# Tiny_Radio_Reference_Build_V2_RC5_2020-0.net
KiCad netlist of a schematic drawn in EasyEDA
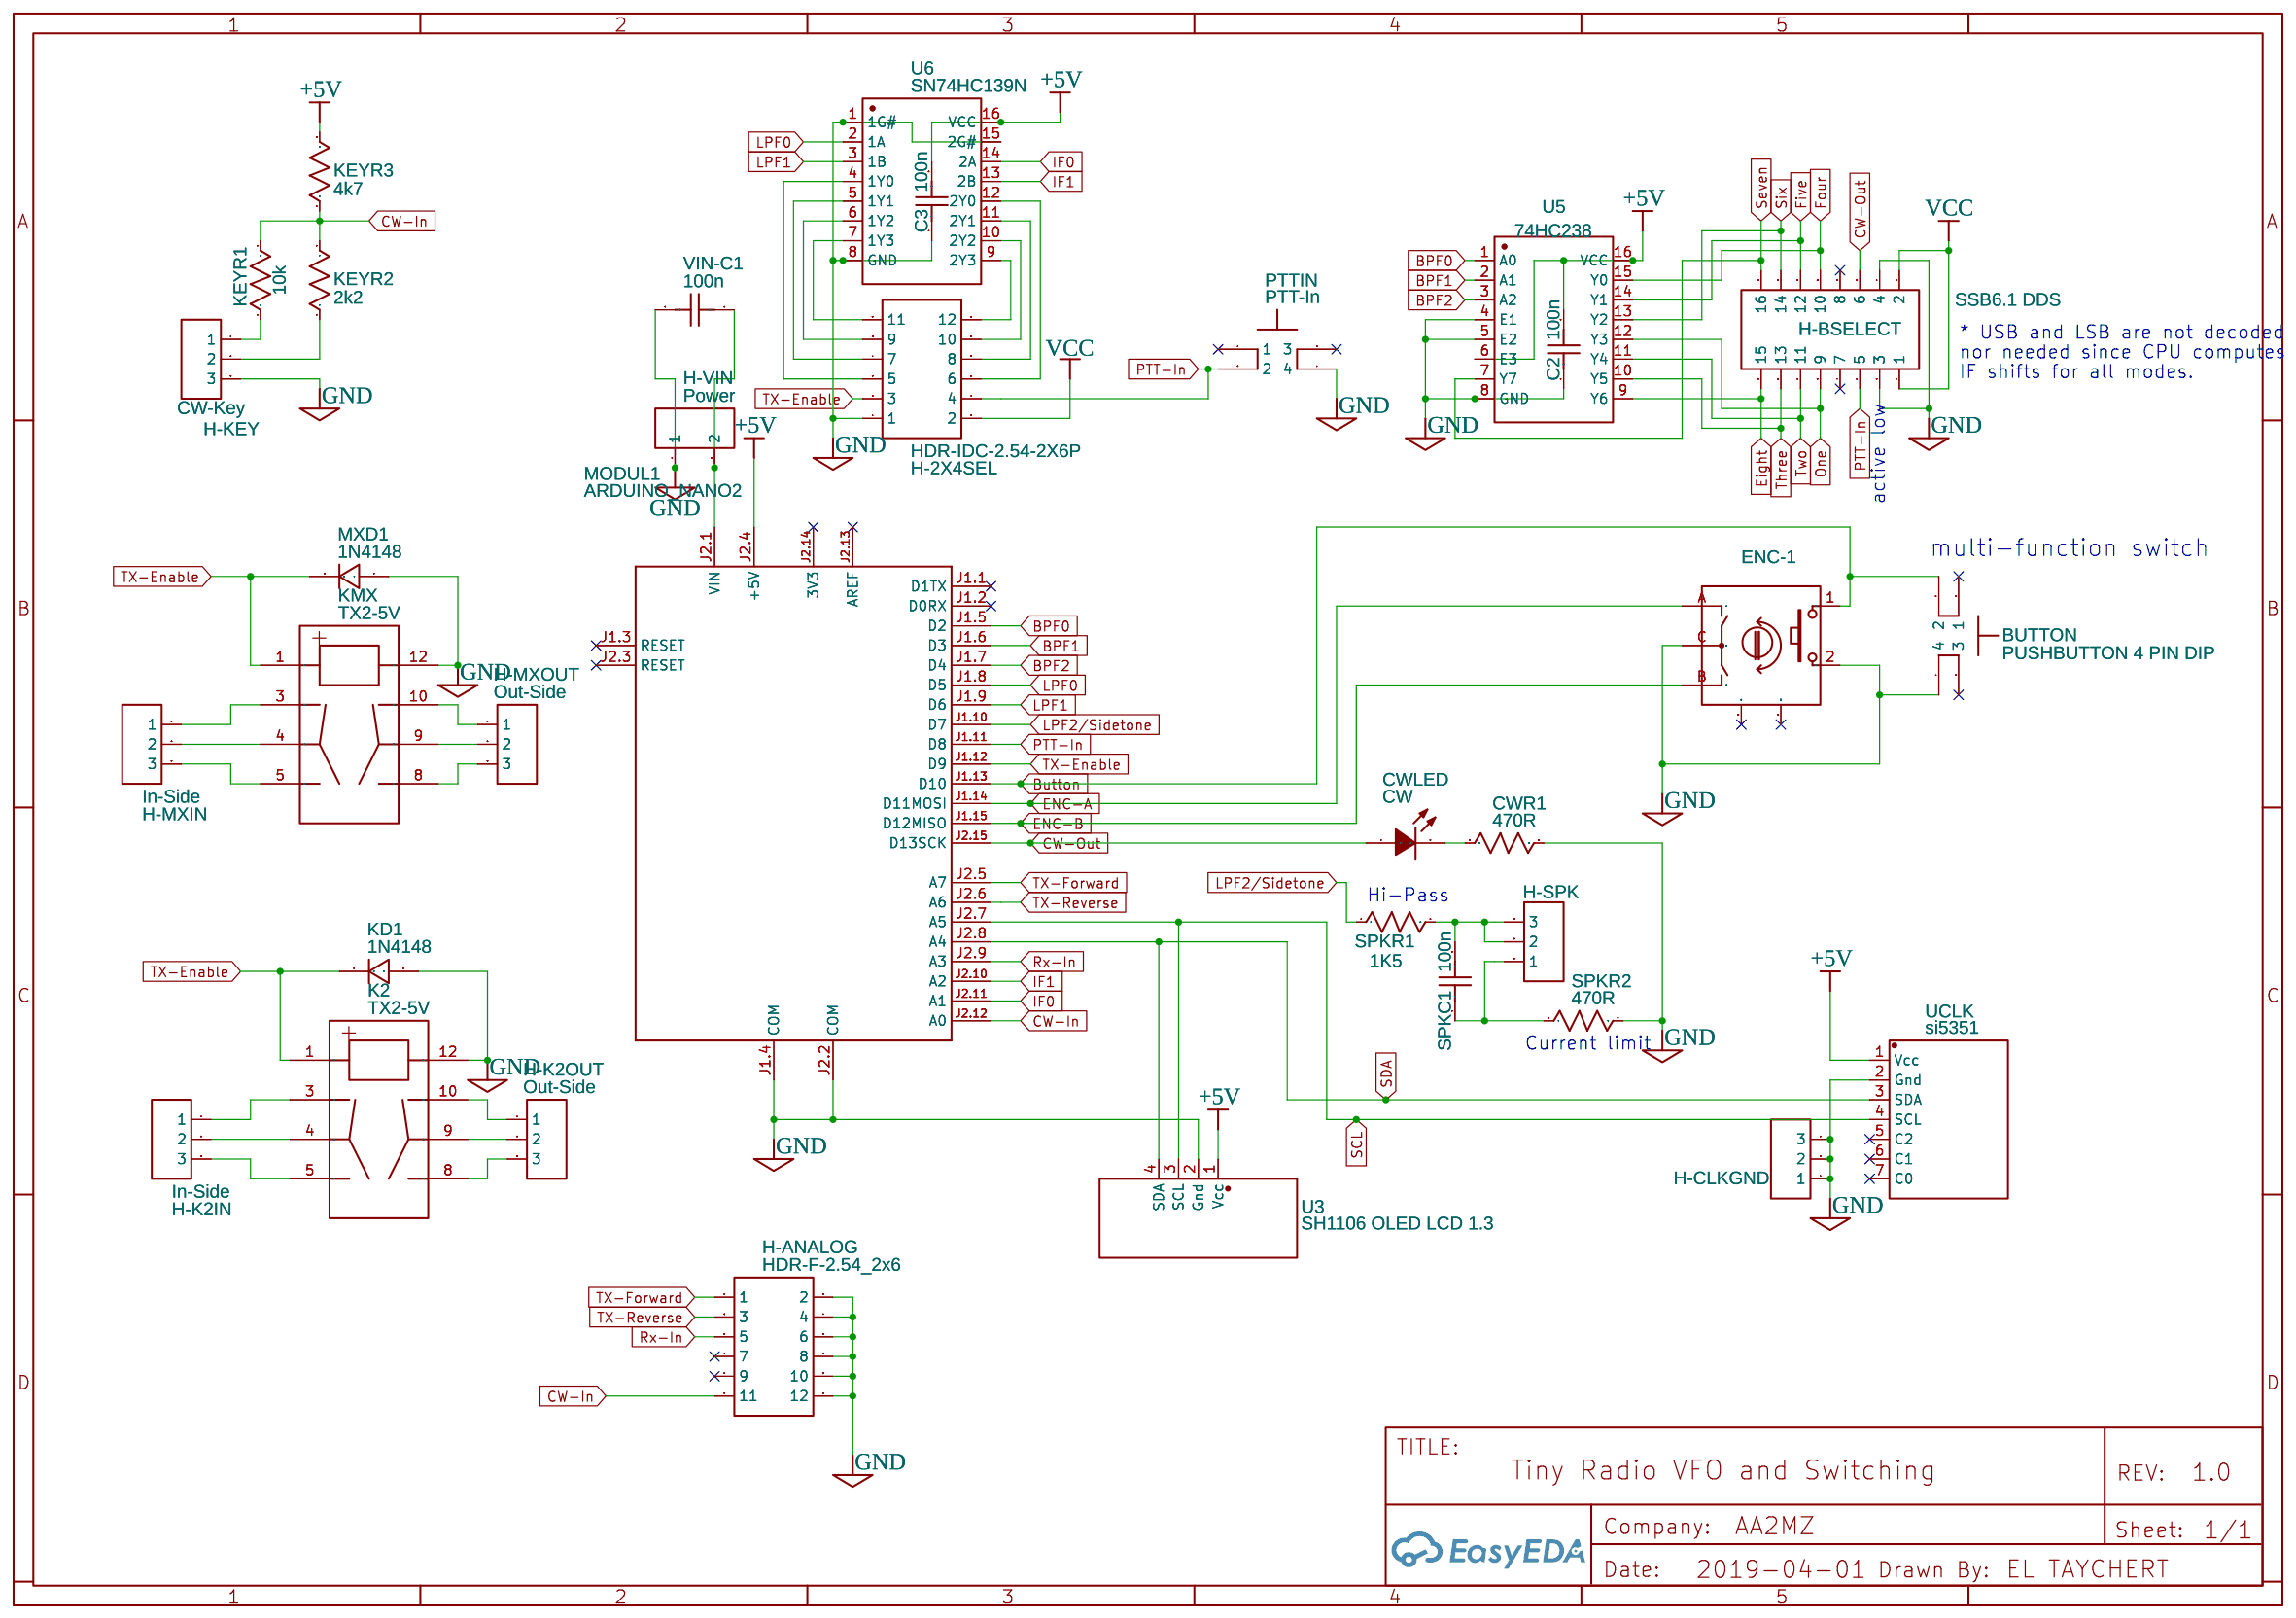
[diagram p0: Sheet_1]
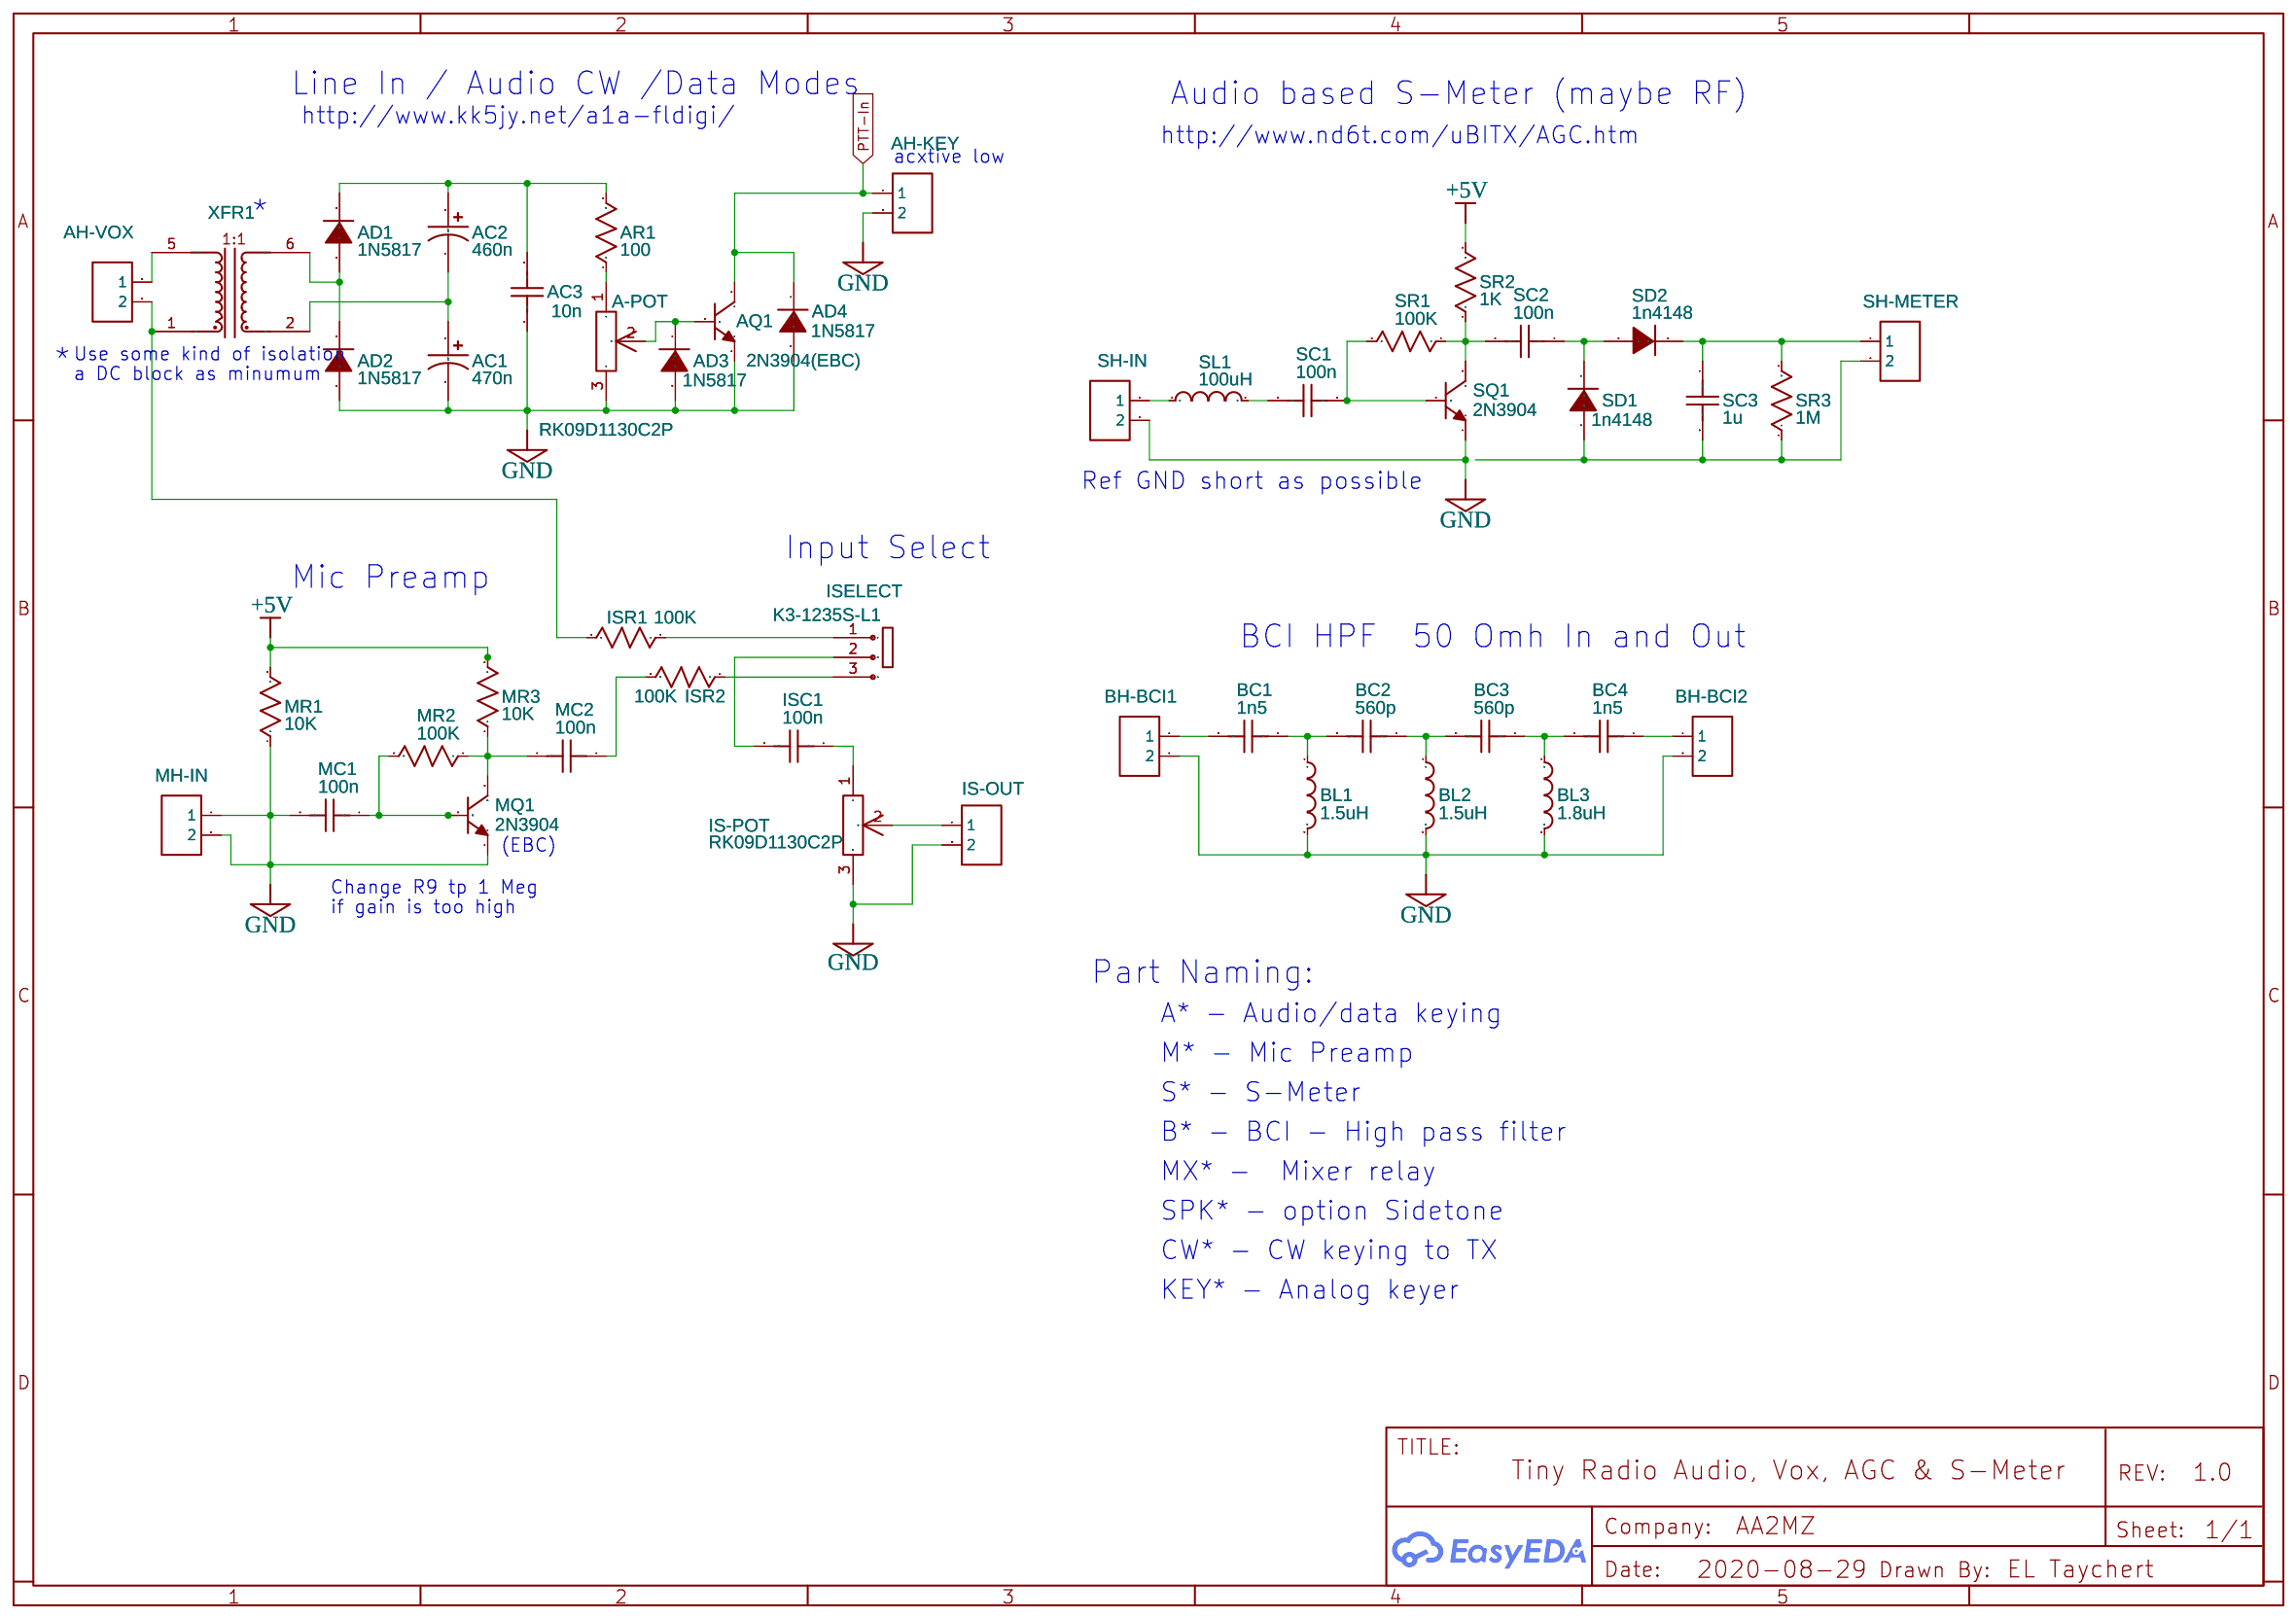
[diagram p1: Sheet_2]

(export (version "E")
  (design (tool "Eeschema 10.0.6"))
  (components
    (comp (ref "BUTTON")
      (value "PUSHBUTTON 4 PIN DIP")
      (fields (field (name "BOM_Manufacturer Part") "Pushbutton"))
      (libsource (lib "") (part "Unknown_985_315"))
    )
    (comp (ref "C2") (value "100n") (libsource (lib "") (part "C_RAD-0.2_US")))
    (comp (ref "C3") (value "100n") (libsource (lib "") (part "C_RAD-0.2_US")))
    (comp (ref "CWLED")
      (value "CW")
      (fields
        (field (name "BOM_Manufacturer Part") "204-10SURD/S530-A3")
        (field (name "BOM_Supplier Part") "C99772")
      )
      (libsource (lib "") (part "Unknown_705_415"))
    )
    (comp (ref "CWR1") (value "470R") (libsource (lib "") (part "Res_AXIAL-0.3(1/8W)_US_2")))
    (comp (ref "ENC-1")
      (value "PEC11R-4015F-S0024")
      (fields (field (name "BOM_Supplier Part") "C143789"))
      (libsource (lib "") (part "Unknown_885_330"))
    )
    (comp (ref "H-2X4SEL")
      (value "HDR-IDC-2.54-2X6P")
      (fields
        (field (name "BOM_Manufacturer Part") "IDC Box 2X6 2.54MM")
        (field (name "BOM_Supplier Part") "C9136")
      )
      (libsource (lib "") (part "HDR-IDC-2.54-2X6P"))
    )
    (comp (ref "H-ANALOG")
      (value "HDR-F-2.54_2x6")
      (fields (field (name "BOM_Supplier Part") "C36191"))
      (libsource (lib "") (part "HDR-F-2.54_2x6"))
    )
    (comp (ref "H-BSELECT")
      (value "SSB6.1 DDS")
      (fields
        (field (name "BOM_Manufacturer Part") "IDC Box 2.54mm 16P　Straight")
        (field (name "BOM_Supplier Part") "C3406")
      )
      (libsource (lib "") (part "HDR-IDC-2.54-2X8P"))
    )
    (comp (ref "H-CLKGND")
      (value "Header-Male-2.54_1x3")
      (fields
        (field (name "BOM_Manufacturer Part") "Header2.54mm 1*3P")
        (field (name "BOM_Supplier Part") "C49257")
      )
      (libsource (lib "") (part "Unknown_905_580"))
    )
    (comp (ref "H-K2IN")
      (value "In-Side")
      (fields
        (field (name "BOM_Manufacturer Part") "Header2.54mm 1*3P")
        (field (name "BOM_Supplier Part") "C49257")
      )
      (libsource (lib "") (part "Unknown_85_570"))
    )
    (comp (ref "H-K2OUT")
      (value "Out-Side")
      (fields
        (field (name "BOM_Manufacturer Part") "Header2.54mm 1*3P")
        (field (name "BOM_Supplier Part") "C49257")
      )
      (libsource (lib "") (part "Unknown_265_570"))
    )
    (comp (ref "H-KEY")
      (value "CW-Key")
      (fields (field (name "BOM_Supplier Part") "C180248"))
      (libsource (lib "") (part "HDR-M-2.54_1x3"))
    )
    (comp (ref "H-MXIN")
      (value "In-Side")
      (fields
        (field (name "BOM_Manufacturer Part") "Header2.54mm 1*3P")
        (field (name "BOM_Supplier Part") "C49257")
      )
      (libsource (lib "") (part "Unknown_70_370"))
    )
    (comp (ref "H-MXOUT")
      (value "Out-Side")
      (fields
        (field (name "BOM_Manufacturer Part") "Header2.54mm 1*3P")
        (field (name "BOM_Supplier Part") "C49257")
      )
      (libsource (lib "") (part "Unknown_250_370"))
    )
    (comp (ref "H-SPK")
      (value "Header-Male-2.54_1x3")
      (fields
        (field (name "BOM_Manufacturer Part") "Header2.54mm 1*3P")
        (field (name "BOM_Supplier Part") "C49257")
      )
      (libsource (lib "") (part "Unknown_770_470"))
    )
    (comp (ref "H-VIN")
      (value "Power")
      (fields (field (name "BOM_Manufacturer Part") "826629-2") (field (name "BOM_Supplier Part") "C86471"))
      (libsource (lib "") (part "Unknown_345_215"))
    )
    (comp (ref "K2")
      (value "TX2-5V")
      (fields (field (name "BOM_Supplier Part") "C192257"))
      (libsource (lib "") (part "TX2-5V_1"))
    )
    (comp (ref "KD1")
      (value "1N4148")
      (fields (field (name "BOM_Supplier Part") "C14516"))
      (libsource (lib "") (part "1N4148"))
    )
    (comp (ref "KEYR1") (value "10k") (libsource (lib "") (part "Res_AXIAL-0.3(1/8W)_US")))
    (comp (ref "KEYR2") (value "2k2") (libsource (lib "") (part "Res_AXIAL-0.3(1/8W)_US")))
    (comp (ref "KEYR3") (value "4k7") (libsource (lib "") (part "Res_AXIAL-0.3(1/8W)_US")))
    (comp (ref "KMX")
      (value "TX2-5V")
      (fields (field (name "BOM_Supplier Part") "C192257"))
      (libsource (lib "") (part "TX2-5V"))
    )
    (comp (ref "MODUL1") (value "ARDUINO_NANO2") (libsource (lib "") (part "ARDUINO_NANO2")))
    (comp (ref "MXD1")
      (value "1N4148")
      (fields (field (name "BOM_Supplier Part") "C14516"))
      (libsource (lib "") (part "1N4148_1"))
    )
    (comp (ref "PTTIN")
      (value "PTT-In")
      (fields (field (name "BOM_Manufacturer Part") "Pushbutton"))
      (libsource (lib "") (part "Unknown_640_170"))
    )
    (comp (ref "SPKC1") (value "100n") (libsource (lib "") (part "C_RAD-0.2_US_1")))
    (comp (ref "SPKR1") (value "1K5") (libsource (lib "") (part "Res_AXIAL-0.3(1/8W)_US_1")))
    (comp (ref "SPKR2") (value "470R") (libsource (lib "") (part "Res_AXIAL-0.3(1/8W)_US_1")))
    (comp (ref "U3")
      (value "SH1106 OLED LCD 1.3")
      (fields (field (name "BOM_Manufacturer Part") "OLED_LCD_SH1106"))
      (libsource (lib "") (part "Unknown_620_590"))
    )
    (comp (ref "U5")
      (value "74HC238")
      (fields
        (field (name "BOM_Manufacturer Part") "CD74HC238E")
        (field (name "BOM_Supplier Part") "820490127")
      )
      (libsource (lib "") (part "Unknown_780_160"))
    )
    (comp (ref "U6")
      (value "SN74HC139N")
      (fields (field (name "BOM_Supplier Part") "C2906"))
      (libsource (lib "") (part "SN74HC139N"))
    )
    (comp (ref "UCLK")
      (value "si5351")
      (fields (field (name "BOM_Manufacturer Part") "?"))
      (libsource (lib "") (part "Unknown_980_560"))
    )
    (comp (ref "VIN-C1") (value "100n") (libsource (lib "") (part "Cap_RAD-0.2_US")))
    (comp (ref "A-POT")
      (value "RK09D1130C2P")
      (fields (field (name "BOM_Supplier Part") "C361173"))
      (libsource (lib "") (part "RK09D1130C2P_1"))
    )
    (comp (ref "AC1") (value "470n") (libsource (lib "") (part "CE_TH_D5.0×F2.0_US")))
    (comp (ref "AC2") (value "460n") (libsource (lib "") (part "CE_TH_D5.0×F2.0_US")))
    (comp (ref "AC3") (value "10n") (libsource (lib "") (part "C_0603_US_4")))
    (comp (ref "AD1")
      (value "1N5817")
      (fields (field (name "BOM_Supplier Part") "C256526"))
      (libsource (lib "") (part "1N5817_C256526"))
    )
    (comp (ref "AD2")
      (value "1N5817")
      (fields (field (name "BOM_Supplier Part") "C256526"))
      (libsource (lib "") (part "1N5817_C256526"))
    )
    (comp (ref "AD3")
      (value "1N5817")
      (fields (field (name "BOM_Supplier Part") "C256526"))
      (libsource (lib "") (part "1N5817_C256526"))
    )
    (comp (ref "AD4")
      (value "1N5817")
      (fields (field (name "BOM_Supplier Part") "C256526"))
      (libsource (lib "") (part "1N5817_C256526"))
    )
    (comp (ref "AH-KEY")
      (value "HDR-M-2.54_1x2")
      (fields (field (name "BOM_Supplier Part") "C124375"))
      (libsource (lib "") (part "HDR-M-2.54_1x2_6"))
    )
    (comp (ref "AH-VOX")
      (value "HDR-M-2.54_1x2")
      (fields (field (name "BOM_Supplier Part") "C124375"))
      (libsource (lib "") (part "HDR-M-2.54_1x2_5"))
    )
    (comp (ref "AQ1")
      (value "2N3904(EBC)")
      (fields (field (name "BOM_Manufacturer Part") "2N3904") (field (name "BOM_Supplier Part") "C118538"))
      (libsource (lib "") (part "2N3904(TO-92)_1"))
    )
    (comp (ref "AR1") (value "100") (libsource (lib "") (part "R_0603_US_4")))
    (comp (ref "BC1") (value "1n5") (libsource (lib "") (part "C_0603_US_3")))
    (comp (ref "BC2") (value "560p") (libsource (lib "") (part "C_0603_US_3")))
    (comp (ref "BC3") (value "560p") (libsource (lib "") (part "C_0603_US_3")))
    (comp (ref "BC4") (value "1n5") (libsource (lib "") (part "C_0603_US_3")))
    (comp (ref "BH-BCI1")
      (value "HDR-M-2.54_1x2")
      (fields (field (name "BOM_Supplier Part") "C124375"))
      (libsource (lib "") (part "HDR-M-2.54_1x2_1"))
    )
    (comp (ref "BH-BCI2")
      (value "HDR-M-2.54_1x2")
      (fields (field (name "BOM_Supplier Part") "C124375"))
      (libsource (lib "") (part "HDR-M-2.54_1x2_7"))
    )
    (comp (ref "BL1") (value "1.5uH") (libsource (lib "") (part "L_AXIAL-0.5_US_2")))
    (comp (ref "BL2") (value "1.5uH") (libsource (lib "") (part "L_AXIAL-0.5_US_2")))
    (comp (ref "BL3") (value "1.8uH") (libsource (lib "") (part "L_AXIAL-0.5_US_1")))
    (comp (ref "IS-OUT")
      (value "HDR-M-2.54_1x2")
      (fields (field (name "BOM_Supplier Part") "C124375"))
      (libsource (lib "") (part "HDR-M-2.54_1x2_2"))
    )
    (comp (ref "IS-POT")
      (value "RK09D1130C2P")
      (fields (field (name "BOM_Supplier Part") "C361173"))
      (libsource (lib "") (part "RK09D1130C2P"))
    )
    (comp (ref "ISC1") (value "100n") (libsource (lib "") (part "C_0603_US")))
    (comp (ref "ISELECT")
      (value "K3-1235S-L1")
      (fields (field (name "BOM_Supplier Part") "C223838"))
      (libsource (lib "") (part "K3-1235S-L1"))
    )
    (comp (ref "ISR1") (value "100K") (libsource (lib "") (part "R_0603_US_2")))
    (comp (ref "ISR2") (value "100K") (libsource (lib "") (part "R_0603_US_2")))
    (comp (ref "MC1") (value "100n") (libsource (lib "") (part "C_0603_US_2")))
    (comp (ref "MC2") (value "100n") (libsource (lib "") (part "C_0603_US_2")))
    (comp (ref "MH-IN")
      (value "HDR-M-2.54_1x2")
      (fields (field (name "BOM_Supplier Part") "C124375"))
      (libsource (lib "") (part "HDR-M-2.54_1x2"))
    )
    (comp (ref "MQ1")
      (value "2N3904")
      (fields (field (name "BOM_Supplier Part") "C118538"))
      (libsource (lib "") (part "2N3904(TO-92)_2"))
    )
    (comp (ref "MR1") (value "10K") (libsource (lib "") (part "R_0603_US_1")))
    (comp (ref "MR2") (value "100K") (libsource (lib "") (part "R_0603_US_3")))
    (comp (ref "MR3") (value "10K") (libsource (lib "") (part "R_0603_US_1")))
    (comp (ref "SC1") (value "100n") (libsource (lib "") (part "C_0603_US_1")))
    (comp (ref "SC2") (value "100n") (libsource (lib "") (part "C_0603_US_1")))
    (comp (ref "SC3") (value "1u") (libsource (lib "") (part "C_0603_US_5")))
    (comp (ref "SD1")
      (value "1n4148")
      (fields (field (name "BOM_Manufacturer Part") "1N5817") (field (name "BOM_Supplier Part") "C256526"))
      (libsource (lib "") (part "1N5817_C256526_1"))
    )
    (comp (ref "SD2")
      (value "1n4148")
      (fields (field (name "BOM_Manufacturer Part") "1N5817") (field (name "BOM_Supplier Part") "C256526"))
      (libsource (lib "") (part "1N5817_C256526_2"))
    )
    (comp (ref "SH-IN")
      (value "HDR-M-2.54_1x2")
      (fields (field (name "BOM_Supplier Part") "C124375"))
      (libsource (lib "") (part "HDR-M-2.54_1x2_3"))
    )
    (comp (ref "SH-METER")
      (value "HDR-M-2.54_1x2")
      (fields (field (name "BOM_Supplier Part") "C124375"))
      (libsource (lib "") (part "HDR-M-2.54_1x2_4"))
    )
    (comp (ref "SL1") (value "100uH") (libsource (lib "") (part "L_AXIAL-0.5_US")))
    (comp (ref "SQ1")
      (value "2N3904")
      (fields (field (name "BOM_Supplier Part") "C118538"))
      (libsource (lib "") (part "2N3904(TO-92)"))
    )
    (comp (ref "SR1") (value "100K") (libsource (lib "") (part "R_0603_US_5")))
    (comp (ref "SR2") (value "1K") (libsource (lib "") (part "R_0603_US")))
    (comp (ref "SR3") (value "1M") (libsource (lib "") (part "R_0603_US")))
    (comp (ref "XFR1")
      (value "HR610660")
      (fields (field (name "BOM_Supplier Part") "C48357"))
      (libsource (lib "") (part "HR610660"))
    )
  )
  (nets
    (net (code "1") (name "+5V") (class "Default")
      (node (ref "C2") (pin "2") (pinfunction "2_2") (pintype "unspecified"))
      (node (ref "C3") (pin "2") (pinfunction "2_2") (pintype "unspecified"))
      (node (ref "KEYR3") (pin "2") (pinfunction "2_2") (pintype "unspecified"))
      (node (ref "MODUL1") (pin "J2.4") (pinfunction "+5V_J2.4") (pintype "passive"))
      (node (ref "MR1") (pin "2") (pinfunction "2_2") (pintype "unspecified"))
      (node (ref "MR3") (pin "2") (pinfunction "2_2") (pintype "unspecified"))
      (node (ref "SR2") (pin "2") (pinfunction "2_2") (pintype "unspecified"))
      (node (ref "U3") (pin "1") (pinfunction "Vcc_1") (pintype "unspecified"))
      (node (ref "U5") (pin "16") (pinfunction "VCC_16") (pintype "unspecified"))
      (node (ref "U5") (pin "6") (pinfunction "E3_6") (pintype "unspecified"))
      (node (ref "U6") (pin "16") (pinfunction "VCC_16") (pintype "unspecified"))
      (node (ref "UCLK") (pin "1") (pinfunction "Vcc_1") (pintype "unspecified"))
    )
    (net (code "2") (name "BPF0") (class "Default")
      (node (ref "MODUL1") (pin "J1.5") (pinfunction "D2_J1.5") (pintype "unspecified"))
      (node (ref "U5") (pin "1") (pinfunction "A0_1") (pintype "unspecified"))
    )
    (net (code "3") (name "BPF1") (class "Default")
      (node (ref "MODUL1") (pin "J1.6") (pinfunction "D3_J1.6") (pintype "unspecified"))
      (node (ref "U5") (pin "2") (pinfunction "A1_2") (pintype "unspecified"))
    )
    (net (code "4") (name "BPF2") (class "Default")
      (node (ref "MODUL1") (pin "J1.7") (pinfunction "D4_J1.7") (pintype "unspecified"))
      (node (ref "U5") (pin "3") (pinfunction "A2_3") (pintype "unspecified"))
    )
    (net (code "5") (name "Button") (class "Default")
      (node (ref "BUTTON") (pin "2") (pinfunction "2_2") (pintype "unspecified"))
      (node (ref "ENC-1") (pin "1") (pinfunction "1_1") (pintype "unspecified"))
      (node (ref "MODUL1") (pin "J1.13") (pinfunction "D10_J1.13") (pintype "unspecified"))
    )
    (net (code "6") (name "CW-In") (class "Default")
      (node (ref "H-ANALOG") (pin "11") (pinfunction "11_11") (pintype "input"))
      (node (ref "KEYR1") (pin "2") (pinfunction "2_2") (pintype "unspecified"))
      (node (ref "KEYR2") (pin "2") (pinfunction "2_2") (pintype "unspecified"))
      (node (ref "KEYR3") (pin "1") (pinfunction "1_1") (pintype "unspecified"))
      (node (ref "MODUL1") (pin "J2.12") (pinfunction "A0_J2.12") (pintype "unspecified"))
    )
    (net (code "7") (name "CW-Out") (class "Default")
      (node (ref "CWLED") (pin "1") (pinfunction "A_1") (pintype "unspecified"))
      (node (ref "H-BSELECT") (pin "6") (pinfunction "6_6") (pintype "unspecified"))
      (node (ref "MODUL1") (pin "J2.15") (pinfunction "D13SCK_J2.15") (pintype "unspecified"))
    )
    (net (code "8") (name "ENC-A") (class "Default")
      (node (ref "ENC-1") (pin "A") (pinfunction "A_A") (pintype "unspecified"))
      (node (ref "MODUL1") (pin "J1.14") (pinfunction "D11MOSI_J1.14") (pintype "unspecified"))
    )
    (net (code "9") (name "ENC-B") (class "Default")
      (node (ref "ENC-1") (pin "B") (pinfunction "B_B") (pintype "unspecified"))
      (node (ref "MODUL1") (pin "J1.15") (pinfunction "D12MISO_J1.15") (pintype "unspecified"))
    )
    (net (code "10") (name "Eight") (class "Default")
      (node (ref "H-BSELECT") (pin "15") (pinfunction "15_15") (pintype "unspecified"))
      (node (ref "U5") (pin "9") (pinfunction "Y6_9") (pintype "unspecified"))
    )
    (net (code "11") (name "Five") (class "Default")
      (node (ref "H-BSELECT") (pin "12") (pinfunction "12_12") (pintype "unspecified"))
      (node (ref "U5") (pin "14") (pinfunction "Y1_14") (pintype "unspecified"))
    )
    (net (code "12") (name "Four") (class "Default")
      (node (ref "H-BSELECT") (pin "10") (pinfunction "10_10") (pintype "unspecified"))
      (node (ref "U5") (pin "15") (pinfunction "Y0_15") (pintype "unspecified"))
    )
    (net (code "13") (name "GND") (class "Default")
      (node (ref "A-POT") (pin "3") (pinfunction "3_3") (pintype "unspecified"))
      (node (ref "AC1") (pin "2") (pinfunction "2_2") (pintype "unspecified"))
      (node (ref "AC3") (pin "1") (pinfunction "1_1") (pintype "unspecified"))
      (node (ref "AD2") (pin "2") (pinfunction "A_2") (pintype "unspecified"))
      (node (ref "AD3") (pin "2") (pinfunction "A_2") (pintype "unspecified"))
      (node (ref "AD4") (pin "2") (pinfunction "A_2") (pintype "unspecified"))
      (node (ref "AH-KEY") (pin "2") (pinfunction "2_2") (pintype "unspecified"))
      (node (ref "AQ1") (pin "1") (pinfunction "E_1") (pintype "unspecified"))
      (node (ref "BH-BCI1") (pin "2") (pinfunction "2_2") (pintype "unspecified"))
      (node (ref "BH-BCI2") (pin "2") (pinfunction "2_2") (pintype "unspecified"))
      (node (ref "BL1") (pin "2") (pinfunction "2_2") (pintype "unspecified"))
      (node (ref "BL2") (pin "2") (pinfunction "2_2") (pintype "unspecified"))
      (node (ref "BL3") (pin "2") (pinfunction "2_2") (pintype "unspecified"))
      (node (ref "BUTTON") (pin "4") (pinfunction "4_4") (pintype "unspecified"))
      (node (ref "C2") (pin "1") (pinfunction "1_1") (pintype "unspecified"))
      (node (ref "C3") (pin "1") (pinfunction "1_1") (pintype "unspecified"))
      (node (ref "CWR1") (pin "2") (pinfunction "2_2") (pintype "unspecified"))
      (node (ref "ENC-1") (pin "2") (pinfunction "2_2") (pintype "unspecified"))
      (node (ref "ENC-1") (pin "C") (pinfunction "C_C") (pintype "unspecified"))
      (node (ref "H-2X4SEL") (pin "1") (pinfunction "1_1") (pintype "unspecified"))
      (node (ref "H-ANALOG") (pin "10") (pinfunction "10_10") (pintype "input"))
      (node (ref "H-ANALOG") (pin "12") (pinfunction "12_12") (pintype "input"))
      (node (ref "H-ANALOG") (pin "2") (pinfunction "2_2") (pintype "input"))
      (node (ref "H-ANALOG") (pin "4") (pinfunction "4_4") (pintype "input"))
      (node (ref "H-ANALOG") (pin "6") (pinfunction "6_6") (pintype "input"))
      (node (ref "H-ANALOG") (pin "8") (pinfunction "8_8") (pintype "input"))
      (node (ref "H-BSELECT") (pin "3") (pinfunction "3_3") (pintype "unspecified"))
      (node (ref "H-BSELECT") (pin "4") (pinfunction "4_4") (pintype "unspecified"))
      (node (ref "H-CLKGND") (pin "1") (pinfunction "1_1") (pintype "input"))
      (node (ref "H-CLKGND") (pin "2") (pinfunction "2_2") (pintype "input"))
      (node (ref "H-CLKGND") (pin "3") (pinfunction "3_3") (pintype "input"))
      (node (ref "H-KEY") (pin "3") (pinfunction "3_3") (pintype "input"))
      (node (ref "H-VIN") (pin "1") (pinfunction "1_1") (pintype "unspecified"))
      (node (ref "IS-OUT") (pin "2") (pinfunction "2_2") (pintype "unspecified"))
      (node (ref "IS-POT") (pin "3") (pinfunction "3_3") (pintype "unspecified"))
      (node (ref "K2") (pin "12") (pinfunction "12_12") (pintype "unspecified"))
      (node (ref "KD1") (pin "1") (pinfunction "1_1") (pintype "unspecified"))
      (node (ref "KMX") (pin "12") (pinfunction "12_12") (pintype "unspecified"))
      (node (ref "MC1") (pin "2") (pinfunction "2_2") (pintype "unspecified"))
      (node (ref "MH-IN") (pin "1") (pinfunction "1_1") (pintype "unspecified"))
      (node (ref "MH-IN") (pin "2") (pinfunction "2_2") (pintype "unspecified"))
      (node (ref "MODUL1") (pin "J1.4") (pinfunction "COM_J1.4") (pintype "passive"))
      (node (ref "MODUL1") (pin "J2.2") (pinfunction "COM_J2.2") (pintype "passive"))
      (node (ref "MQ1") (pin "1") (pinfunction "E_1") (pintype "unspecified"))
      (node (ref "MR1") (pin "1") (pinfunction "1_1") (pintype "unspecified"))
      (node (ref "MXD1") (pin "1") (pinfunction "1_1") (pintype "unspecified"))
      (node (ref "PTTIN") (pin "4") (pinfunction "4_4") (pintype "unspecified"))
      (node (ref "SH-IN") (pin "2") (pinfunction "2_2") (pintype "unspecified"))
      (node (ref "SPKR2") (pin "2") (pinfunction "2_2") (pintype "unspecified"))
      (node (ref "SQ1") (pin "1") (pinfunction "E_1") (pintype "unspecified"))
      (node (ref "U3") (pin "2") (pinfunction "Gnd_2") (pintype "unspecified"))
      (node (ref "U5") (pin "4") (pinfunction "E1_4") (pintype "unspecified"))
      (node (ref "U5") (pin "5") (pinfunction "E2_5") (pintype "unspecified"))
      (node (ref "U5") (pin "8") (pinfunction "GND_8") (pintype "unspecified"))
      (node (ref "U6") (pin "1") (pinfunction "1G#_1") (pintype "unspecified"))
      (node (ref "U6") (pin "15") (pinfunction "2G#_15") (pintype "unspecified"))
      (node (ref "U6") (pin "8") (pinfunction "GND_8") (pintype "unspecified"))
      (node (ref "UCLK") (pin "2") (pinfunction "Gnd_2") (pintype "unspecified"))
      (node (ref "VIN-C1") (pin "2") (pinfunction "2_2") (pintype "unspecified"))
    )
    (net (code "14") (name "IF0") (class "Default")
      (node (ref "MODUL1") (pin "J2.11") (pinfunction "A1_J2.11") (pintype "unspecified"))
      (node (ref "U6") (pin "14") (pinfunction "2A_14") (pintype "unspecified"))
    )
    (net (code "15") (name "IF1") (class "Default")
      (node (ref "MODUL1") (pin "J2.10") (pinfunction "A2_J2.10") (pintype "unspecified"))
      (node (ref "U6") (pin "13") (pinfunction "2B_13") (pintype "unspecified"))
    )
    (net (code "16") (name "LPF0") (class "Default")
      (node (ref "MODUL1") (pin "J1.8") (pinfunction "D5_J1.8") (pintype "unspecified"))
      (node (ref "U6") (pin "2") (pinfunction "1A_2") (pintype "unspecified"))
    )
    (net (code "17") (name "LPF1") (class "Default")
      (node (ref "MODUL1") (pin "J1.9") (pinfunction "D6_J1.9") (pintype "unspecified"))
      (node (ref "U6") (pin "3") (pinfunction "1B_3") (pintype "unspecified"))
    )
    (net (code "18") (name "LPF2{slash}Sidetone") (class "Default")
      (node (ref "MODUL1") (pin "J1.10") (pinfunction "D7_J1.10") (pintype "unspecified"))
      (node (ref "SPKR1") (pin "1") (pinfunction "1_1") (pintype "unspecified"))
    )
    (net (code "19") (name "Net-(A-POT-Pad1)") (class "Default")
      (node (ref "A-POT") (pin "1") (pinfunction "1_1") (pintype "unspecified"))
      (node (ref "AR1") (pin "1") (pinfunction "1_1") (pintype "unspecified"))
    )
    (net (code "20") (name "Net-(AC1-Pad1)") (class "Default")
      (node (ref "AC1") (pin "1") (pinfunction "1_1") (pintype "unspecified"))
      (node (ref "AC2") (pin "2") (pinfunction "2_2") (pintype "unspecified"))
      (node (ref "XFR1") (pin "2") (pinfunction "2_2") (pintype "unspecified"))
    )
    (net (code "21") (name "Net-(AD1-A)") (class "Default")
      (node (ref "AD1") (pin "2") (pinfunction "A_2") (pintype "unspecified"))
      (node (ref "AD2") (pin "1") (pinfunction "K_1") (pintype "unspecified"))
      (node (ref "XFR1") (pin "6") (pinfunction "6_6") (pintype "unspecified"))
    )
    (net (code "22") (name "Net-(AD1-K)") (class "Default")
      (node (ref "AC2") (pin "1") (pinfunction "1_1") (pintype "unspecified"))
      (node (ref "AC3") (pin "2") (pinfunction "2_2") (pintype "unspecified"))
      (node (ref "AD1") (pin "1") (pinfunction "K_1") (pintype "unspecified"))
      (node (ref "AR1") (pin "2") (pinfunction "2_2") (pintype "unspecified"))
    )
    (net (code "23") (name "Net-(AD3-K)") (class "Default")
      (node (ref "A-POT") (pin "2") (pinfunction "2_2") (pintype "unspecified"))
      (node (ref "AD3") (pin "1") (pinfunction "K_1") (pintype "unspecified"))
      (node (ref "AQ1") (pin "2") (pinfunction "B_2") (pintype "unspecified"))
    )
    (net (code "24") (name "Net-(AH-VOX-Pad1)") (class "Default")
      (node (ref "AH-VOX") (pin "1") (pinfunction "1_1") (pintype "unspecified"))
      (node (ref "XFR1") (pin "5") (pinfunction "5_5") (pintype "unspecified"))
    )
    (net (code "25") (name "Net-(AH-VOX-Pad2)") (class "Default")
      (node (ref "AH-VOX") (pin "2") (pinfunction "2_2") (pintype "unspecified"))
      (node (ref "ISR1") (pin "2") (pinfunction "2_2") (pintype "unspecified"))
      (node (ref "XFR1") (pin "1") (pinfunction "1_1") (pintype "unspecified"))
    )
    (net (code "26") (name "Net-(BC1-Pad1)") (class "Default")
      (node (ref "BC1") (pin "1") (pinfunction "1_1") (pintype "unspecified"))
      (node (ref "BC2") (pin "2") (pinfunction "2_2") (pintype "unspecified"))
      (node (ref "BL1") (pin "1") (pinfunction "1_1") (pintype "unspecified"))
    )
    (net (code "27") (name "Net-(BC1-Pad2)") (class "Default")
      (node (ref "BC1") (pin "2") (pinfunction "2_2") (pintype "unspecified"))
      (node (ref "BH-BCI1") (pin "1") (pinfunction "1_1") (pintype "unspecified"))
    )
    (net (code "28") (name "Net-(BC2-Pad1)") (class "Default")
      (node (ref "BC2") (pin "1") (pinfunction "1_1") (pintype "unspecified"))
      (node (ref "BC3") (pin "2") (pinfunction "2_2") (pintype "unspecified"))
      (node (ref "BL2") (pin "1") (pinfunction "1_1") (pintype "unspecified"))
    )
    (net (code "29") (name "Net-(BC3-Pad1)") (class "Default")
      (node (ref "BC3") (pin "1") (pinfunction "1_1") (pintype "unspecified"))
      (node (ref "BC4") (pin "2") (pinfunction "2_2") (pintype "unspecified"))
      (node (ref "BL3") (pin "1") (pinfunction "1_1") (pintype "unspecified"))
    )
    (net (code "30") (name "Net-(BC4-Pad1)") (class "Default")
      (node (ref "BC4") (pin "1") (pinfunction "1_1") (pintype "unspecified"))
      (node (ref "BH-BCI2") (pin "1") (pinfunction "1_1") (pintype "unspecified"))
    )
    (net (code "31") (name "Net-(CWLED-K)") (class "Default")
      (node (ref "CWLED") (pin "2") (pinfunction "K_2") (pintype "unspecified"))
      (node (ref "CWR1") (pin "1") (pinfunction "1_1") (pintype "unspecified"))
    )
    (net (code "32") (name "Net-(H-K2IN-Pad1)") (class "Default")
      (node (ref "H-K2IN") (pin "1") (pinfunction "1_1") (pintype "input"))
      (node (ref "K2") (pin "3") (pinfunction "3_3") (pintype "unspecified"))
    )
    (net (code "33") (name "Net-(H-K2IN-Pad2)") (class "Default")
      (node (ref "H-K2IN") (pin "2") (pinfunction "2_2") (pintype "input"))
      (node (ref "K2") (pin "4") (pinfunction "4_4") (pintype "unspecified"))
    )
    (net (code "34") (name "Net-(H-K2IN-Pad3)") (class "Default")
      (node (ref "H-K2IN") (pin "3") (pinfunction "3_3") (pintype "input"))
      (node (ref "K2") (pin "5") (pinfunction "5_5") (pintype "unspecified"))
    )
    (net (code "35") (name "Net-(H-K2OUT-Pad1)") (class "Default")
      (node (ref "H-K2OUT") (pin "1") (pinfunction "1_1") (pintype "input"))
      (node (ref "K2") (pin "10") (pinfunction "10_10") (pintype "unspecified"))
    )
    (net (code "36") (name "Net-(H-K2OUT-Pad2)") (class "Default")
      (node (ref "H-K2OUT") (pin "2") (pinfunction "2_2") (pintype "input"))
      (node (ref "K2") (pin "9") (pinfunction "9_9") (pintype "unspecified"))
    )
    (net (code "37") (name "Net-(H-K2OUT-Pad3)") (class "Default")
      (node (ref "H-K2OUT") (pin "3") (pinfunction "3_3") (pintype "input"))
      (node (ref "K2") (pin "8") (pinfunction "8_8") (pintype "unspecified"))
    )
    (net (code "38") (name "Net-(H-KEY-Pad1)") (class "Default")
      (node (ref "H-KEY") (pin "1") (pinfunction "1_1") (pintype "input"))
      (node (ref "KEYR1") (pin "1") (pinfunction "1_1") (pintype "unspecified"))
    )
    (net (code "39") (name "Net-(H-KEY-Pad2)") (class "Default")
      (node (ref "H-KEY") (pin "2") (pinfunction "2_2") (pintype "input"))
      (node (ref "KEYR2") (pin "1") (pinfunction "1_1") (pintype "unspecified"))
    )
    (net (code "40") (name "Net-(H-MXIN-Pad1)") (class "Default")
      (node (ref "H-MXIN") (pin "1") (pinfunction "1_1") (pintype "input"))
      (node (ref "KMX") (pin "3") (pinfunction "3_3") (pintype "unspecified"))
    )
    (net (code "41") (name "Net-(H-MXIN-Pad2)") (class "Default")
      (node (ref "H-MXIN") (pin "2") (pinfunction "2_2") (pintype "input"))
      (node (ref "KMX") (pin "4") (pinfunction "4_4") (pintype "unspecified"))
    )
    (net (code "42") (name "Net-(H-MXIN-Pad3)") (class "Default")
      (node (ref "H-MXIN") (pin "3") (pinfunction "3_3") (pintype "input"))
      (node (ref "KMX") (pin "5") (pinfunction "5_5") (pintype "unspecified"))
    )
    (net (code "43") (name "Net-(H-MXOUT-Pad1)") (class "Default")
      (node (ref "H-MXOUT") (pin "1") (pinfunction "1_1") (pintype "input"))
      (node (ref "KMX") (pin "10") (pinfunction "10_10") (pintype "unspecified"))
    )
    (net (code "44") (name "Net-(H-MXOUT-Pad2)") (class "Default")
      (node (ref "H-MXOUT") (pin "2") (pinfunction "2_2") (pintype "input"))
      (node (ref "KMX") (pin "9") (pinfunction "9_9") (pintype "unspecified"))
    )
    (net (code "45") (name "Net-(H-MXOUT-Pad3)") (class "Default")
      (node (ref "H-MXOUT") (pin "3") (pinfunction "3_3") (pintype "input"))
      (node (ref "KMX") (pin "8") (pinfunction "8_8") (pintype "unspecified"))
    )
    (net (code "46") (name "Net-(H-SPK-Pad1)") (class "Default")
      (node (ref "H-SPK") (pin "1") (pinfunction "1_1") (pintype "input"))
      (node (ref "SPKC1") (pin "1") (pinfunction "1_1") (pintype "unspecified"))
      (node (ref "SPKR2") (pin "1") (pinfunction "1_1") (pintype "unspecified"))
    )
    (net (code "47") (name "Net-(H-SPK-Pad2)") (class "Default")
      (node (ref "H-SPK") (pin "2") (pinfunction "2_2") (pintype "input"))
      (node (ref "H-SPK") (pin "3") (pinfunction "3_3") (pintype "input"))
      (node (ref "SPKC1") (pin "2") (pinfunction "2_2") (pintype "unspecified"))
      (node (ref "SPKR1") (pin "2") (pinfunction "2_2") (pintype "unspecified"))
    )
    (net (code "48") (name "Net-(IS-OUT-Pad1)") (class "Default")
      (node (ref "IS-OUT") (pin "1") (pinfunction "1_1") (pintype "unspecified"))
      (node (ref "IS-POT") (pin "2") (pinfunction "2_2") (pintype "unspecified"))
    )
    (net (code "49") (name "Net-(IS-POT-Pad1)") (class "Default")
      (node (ref "IS-POT") (pin "1") (pinfunction "1_1") (pintype "unspecified"))
      (node (ref "ISC1") (pin "1") (pinfunction "1_1") (pintype "unspecified"))
    )
    (net (code "50") (name "Net-(ISC1-Pad2)") (class "Default")
      (node (ref "ISC1") (pin "2") (pinfunction "2_2") (pintype "unspecified"))
      (node (ref "ISELECT") (pin "2") (pinfunction "2_2") (pintype "unspecified"))
    )
    (net (code "51") (name "Net-(ISELECT-Pad1)") (class "Default")
      (node (ref "ISELECT") (pin "1") (pinfunction "1_1") (pintype "unspecified"))
      (node (ref "ISR1") (pin "1") (pinfunction "1_1") (pintype "unspecified"))
    )
    (net (code "52") (name "Net-(ISELECT-Pad3)") (class "Default")
      (node (ref "ISELECT") (pin "3") (pinfunction "3_3") (pintype "unspecified"))
      (node (ref "ISR2") (pin "1") (pinfunction "1_1") (pintype "unspecified"))
    )
    (net (code "53") (name "Net-(ISR2-Pad2)") (class "Default")
      (node (ref "ISR2") (pin "2") (pinfunction "2_2") (pintype "unspecified"))
      (node (ref "MC2") (pin "1") (pinfunction "1_1") (pintype "unspecified"))
    )
    (net (code "54") (name "Net-(MODUL1-VIN)") (class "Default")
      (node (ref "H-VIN") (pin "2") (pinfunction "2_2") (pintype "unspecified"))
      (node (ref "MODUL1") (pin "J2.1") (pinfunction "VIN_J2.1") (pintype "passive"))
      (node (ref "VIN-C1") (pin "1") (pinfunction "1_1") (pintype "unspecified"))
    )
    (net (code "55") (name "Net-(MQ1-B)") (class "Default")
      (node (ref "MC1") (pin "1") (pinfunction "1_1") (pintype "unspecified"))
      (node (ref "MQ1") (pin "2") (pinfunction "B_2") (pintype "unspecified"))
      (node (ref "MR2") (pin "2") (pinfunction "2_2") (pintype "unspecified"))
    )
    (net (code "56") (name "Net-(MQ1-C)") (class "Default")
      (node (ref "MC2") (pin "2") (pinfunction "2_2") (pintype "unspecified"))
      (node (ref "MQ1") (pin "3") (pinfunction "C_3") (pintype "unspecified"))
      (node (ref "MR2") (pin "1") (pinfunction "1_1") (pintype "unspecified"))
      (node (ref "MR3") (pin "1") (pinfunction "1_1") (pintype "unspecified"))
    )
    (net (code "57") (name "Net-(SC1-Pad2)") (class "Default")
      (node (ref "SC1") (pin "2") (pinfunction "2_2") (pintype "unspecified"))
      (node (ref "SL1") (pin "2") (pinfunction "2_2") (pintype "unspecified"))
    )
    (net (code "58") (name "Net-(SD1-A)") (class "Default")
      (node (ref "SC3") (pin "2") (pinfunction "2_2") (pintype "unspecified"))
      (node (ref "SD1") (pin "2") (pinfunction "A_2") (pintype "unspecified"))
      (node (ref "SH-METER") (pin "2") (pinfunction "2_2") (pintype "unspecified"))
      (node (ref "SR3") (pin "1") (pinfunction "1_1") (pintype "unspecified"))
    )
    (net (code "59") (name "Net-(SD1-K)") (class "Default")
      (node (ref "SC2") (pin "1") (pinfunction "1_1") (pintype "unspecified"))
      (node (ref "SD1") (pin "1") (pinfunction "K_1") (pintype "unspecified"))
      (node (ref "SD2") (pin "2") (pinfunction "A_2") (pintype "unspecified"))
    )
    (net (code "60") (name "Net-(SD2-K)") (class "Default")
      (node (ref "SC3") (pin "1") (pinfunction "1_1") (pintype "unspecified"))
      (node (ref "SD2") (pin "1") (pinfunction "K_1") (pintype "unspecified"))
      (node (ref "SH-METER") (pin "1") (pinfunction "1_1") (pintype "unspecified"))
      (node (ref "SR3") (pin "2") (pinfunction "2_2") (pintype "unspecified"))
    )
    (net (code "61") (name "Net-(SH-IN-Pad1)") (class "Default")
      (node (ref "SH-IN") (pin "1") (pinfunction "1_1") (pintype "unspecified"))
      (node (ref "SL1") (pin "1") (pinfunction "1_1") (pintype "unspecified"))
    )
    (net (code "62") (name "Net-(SQ1-B)") (class "Default")
      (node (ref "SC1") (pin "1") (pinfunction "1_1") (pintype "unspecified"))
      (node (ref "SQ1") (pin "2") (pinfunction "B_2") (pintype "unspecified"))
      (node (ref "SR1") (pin "2") (pinfunction "2_2") (pintype "unspecified"))
    )
    (net (code "63") (name "Net-(SQ1-C)") (class "Default")
      (node (ref "SC2") (pin "2") (pinfunction "2_2") (pintype "unspecified"))
      (node (ref "SQ1") (pin "3") (pinfunction "C_3") (pintype "unspecified"))
      (node (ref "SR1") (pin "1") (pinfunction "1_1") (pintype "unspecified"))
      (node (ref "SR2") (pin "1") (pinfunction "1_1") (pintype "unspecified"))
    )
    (net (code "64") (name "Net-(U6-1Y0)") (class "Default")
      (node (ref "H-2X4SEL") (pin "5") (pinfunction "5_5") (pintype "unspecified"))
      (node (ref "U6") (pin "4") (pinfunction "1Y0_4") (pintype "unspecified"))
    )
    (net (code "65") (name "Net-(U6-1Y1)") (class "Default")
      (node (ref "H-2X4SEL") (pin "7") (pinfunction "7_7") (pintype "unspecified"))
      (node (ref "U6") (pin "5") (pinfunction "1Y1_5") (pintype "unspecified"))
    )
    (net (code "66") (name "Net-(U6-1Y2)") (class "Default")
      (node (ref "H-2X4SEL") (pin "9") (pinfunction "9_9") (pintype "unspecified"))
      (node (ref "U6") (pin "6") (pinfunction "1Y2_6") (pintype "unspecified"))
    )
    (net (code "67") (name "Net-(U6-1Y3)") (class "Default")
      (node (ref "H-2X4SEL") (pin "11") (pinfunction "11_11") (pintype "unspecified"))
      (node (ref "U6") (pin "7") (pinfunction "1Y3_7") (pintype "unspecified"))
    )
    (net (code "68") (name "Net-(U6-2Y0)") (class "Default")
      (node (ref "H-2X4SEL") (pin "6") (pinfunction "6_6") (pintype "unspecified"))
      (node (ref "U6") (pin "12") (pinfunction "2Y0_12") (pintype "unspecified"))
    )
    (net (code "69") (name "Net-(U6-2Y1)") (class "Default")
      (node (ref "H-2X4SEL") (pin "8") (pinfunction "8_8") (pintype "unspecified"))
      (node (ref "U6") (pin "11") (pinfunction "2Y1_11") (pintype "unspecified"))
    )
    (net (code "70") (name "Net-(U6-2Y2)") (class "Default")
      (node (ref "H-2X4SEL") (pin "10") (pinfunction "10_10") (pintype "unspecified"))
      (node (ref "U6") (pin "10") (pinfunction "2Y2_10") (pintype "unspecified"))
    )
    (net (code "71") (name "Net-(U6-2Y3)") (class "Default")
      (node (ref "H-2X4SEL") (pin "12") (pinfunction "12_12") (pintype "unspecified"))
      (node (ref "U6") (pin "9") (pinfunction "2Y3_9") (pintype "unspecified"))
    )
    (net (code "72") (name "One") (class "Default")
      (node (ref "H-BSELECT") (pin "9") (pinfunction "9_9") (pintype "unspecified"))
      (node (ref "U5") (pin "12") (pinfunction "Y3_12") (pintype "unspecified"))
    )
    (net (code "73") (name "PTT-In") (class "Default")
      (node (ref "AD4") (pin "1") (pinfunction "K_1") (pintype "unspecified"))
      (node (ref "AH-KEY") (pin "1") (pinfunction "1_1") (pintype "unspecified"))
      (node (ref "AQ1") (pin "3") (pinfunction "C_3") (pintype "unspecified"))
      (node (ref "H-2X4SEL") (pin "4") (pinfunction "4_4") (pintype "unspecified"))
      (node (ref "H-BSELECT") (pin "5") (pinfunction "5_5") (pintype "unspecified"))
      (node (ref "MODUL1") (pin "J1.11") (pinfunction "D8_J1.11") (pintype "unspecified"))
      (node (ref "PTTIN") (pin "2") (pinfunction "2_2") (pintype "unspecified"))
    )
    (net (code "74") (name "Rx-In") (class "Default")
      (node (ref "H-ANALOG") (pin "5") (pinfunction "5_5") (pintype "input"))
      (node (ref "MODUL1") (pin "J2.9") (pinfunction "A3_J2.9") (pintype "unspecified"))
    )
    (net (code "75") (name "SCL") (class "Default")
      (node (ref "MODUL1") (pin "J2.7") (pinfunction "A5_J2.7") (pintype "unspecified"))
      (node (ref "U3") (pin "3") (pinfunction "SCL_3") (pintype "unspecified"))
      (node (ref "UCLK") (pin "4") (pinfunction "SCL_4") (pintype "unspecified"))
    )
    (net (code "76") (name "SDA") (class "Default")
      (node (ref "MODUL1") (pin "J2.8") (pinfunction "A4_J2.8") (pintype "unspecified"))
      (node (ref "U3") (pin "4") (pinfunction "SDA_4") (pintype "unspecified"))
      (node (ref "UCLK") (pin "3") (pinfunction "SDA_3") (pintype "unspecified"))
    )
    (net (code "77") (name "Seven") (class "Default")
      (node (ref "H-BSELECT") (pin "16") (pinfunction "16_16") (pintype "unspecified"))
      (node (ref "U5") (pin "7") (pinfunction "Y7_7") (pintype "unspecified"))
    )
    (net (code "78") (name "Six") (class "Default")
      (node (ref "H-BSELECT") (pin "14") (pinfunction "14_14") (pintype "unspecified"))
      (node (ref "U5") (pin "13") (pinfunction "Y2_13") (pintype "unspecified"))
    )
    (net (code "79") (name "TX-Enable") (class "Default")
      (node (ref "H-2X4SEL") (pin "3") (pinfunction "3_3") (pintype "unspecified"))
      (node (ref "K2") (pin "1") (pinfunction "1_1") (pintype "unspecified"))
      (node (ref "KD1") (pin "2") (pinfunction "2_2") (pintype "unspecified"))
      (node (ref "KMX") (pin "1") (pinfunction "1_1") (pintype "unspecified"))
      (node (ref "MODUL1") (pin "J1.12") (pinfunction "D9_J1.12") (pintype "unspecified"))
      (node (ref "MXD1") (pin "2") (pinfunction "2_2") (pintype "unspecified"))
    )
    (net (code "80") (name "TX-Forward") (class "Default")
      (node (ref "H-ANALOG") (pin "1") (pinfunction "1_1") (pintype "input"))
      (node (ref "MODUL1") (pin "J2.5") (pinfunction "A7_J2.5") (pintype "unspecified"))
    )
    (net (code "81") (name "TX-Reverse") (class "Default")
      (node (ref "H-ANALOG") (pin "3") (pinfunction "3_3") (pintype "input"))
      (node (ref "MODUL1") (pin "J2.6") (pinfunction "A6_J2.6") (pintype "unspecified"))
    )
    (net (code "82") (name "Three") (class "Default")
      (node (ref "H-BSELECT") (pin "13") (pinfunction "13_13") (pintype "unspecified"))
      (node (ref "U5") (pin "10") (pinfunction "Y5_10") (pintype "unspecified"))
    )
    (net (code "83") (name "Two") (class "Default")
      (node (ref "H-BSELECT") (pin "11") (pinfunction "11_11") (pintype "unspecified"))
      (node (ref "U5") (pin "11") (pinfunction "Y4_11") (pintype "unspecified"))
    )
    (net (code "84") (name "VCC") (class "Default")
      (node (ref "H-2X4SEL") (pin "2") (pinfunction "2_2") (pintype "unspecified"))
      (node (ref "H-BSELECT") (pin "1") (pinfunction "1_1") (pintype "unspecified"))
      (node (ref "H-BSELECT") (pin "2") (pinfunction "2_2") (pintype "unspecified"))
    )
    (net (code "85") (name "unconnected-(BUTTON-Pad1)") (class "Default")
      (node (ref "BUTTON") (pin "1") (pinfunction "1_1") (pintype "unspecified+no_connect"))
    )
    (net (code "86") (name "unconnected-(BUTTON-Pad3)") (class "Default")
      (node (ref "BUTTON") (pin "3") (pinfunction "3_3") (pintype "unspecified+no_connect"))
    )
    (net (code "87") (name "unconnected-(ENC-1-PadMT1)") (class "Default")
      (node (ref "ENC-1") (pin "MT1") (pinfunction "MT1_MT1") (pintype "unspecified+no_connect"))
    )
    (net (code "88") (name "unconnected-(ENC-1-PadMT2)") (class "Default")
      (node (ref "ENC-1") (pin "MT2") (pinfunction "MT2_MT2") (pintype "unspecified+no_connect"))
    )
    (net (code "89") (name "unconnected-(H-ANALOG-Pad7)") (class "Default")
      (node (ref "H-ANALOG") (pin "7") (pinfunction "7_7") (pintype "input+no_connect"))
    )
    (net (code "90") (name "unconnected-(H-ANALOG-Pad9)") (class "Default")
      (node (ref "H-ANALOG") (pin "9") (pinfunction "9_9") (pintype "input+no_connect"))
    )
    (net (code "91") (name "unconnected-(H-BSELECT-Pad7)") (class "Default")
      (node (ref "H-BSELECT") (pin "7") (pinfunction "7_7") (pintype "unspecified+no_connect"))
    )
    (net (code "92") (name "unconnected-(H-BSELECT-Pad8)") (class "Default")
      (node (ref "H-BSELECT") (pin "8") (pinfunction "8_8") (pintype "unspecified+no_connect"))
    )
    (net (code "93") (name "unconnected-(MODUL1-3V3-PadJ2.14)") (class "Default")
      (node (ref "MODUL1") (pin "J2.14") (pinfunction "3V3_J2.14") (pintype "passive+no_connect"))
    )
    (net (code "94") (name "unconnected-(MODUL1-AREF-PadJ2.13)") (class "Default")
      (node (ref "MODUL1") (pin "J2.13") (pinfunction "AREF_J2.13") (pintype "passive+no_connect"))
    )
    (net (code "95") (name "unconnected-(MODUL1-D0RX-PadJ1.2)") (class "Default")
      (node (ref "MODUL1") (pin "J1.2") (pinfunction "D0RX_J1.2") (pintype "unspecified+no_connect"))
    )
    (net (code "96") (name "unconnected-(MODUL1-D1TX-PadJ1.1)") (class "Default")
      (node (ref "MODUL1") (pin "J1.1") (pinfunction "D1TX_J1.1") (pintype "unspecified+no_connect"))
    )
    (net (code "97") (name "unconnected-(MODUL1-RESET-PadJ1.3)") (class "Default")
      (node (ref "MODUL1") (pin "J1.3") (pinfunction "RESET_J1.3") (pintype "unspecified+no_connect"))
    )
    (net (code "98") (name "unconnected-(MODUL1-RESET-PadJ2.3)") (class "Default")
      (node (ref "MODUL1") (pin "J2.3") (pinfunction "RESET_J2.3") (pintype "unspecified+no_connect"))
    )
    (net (code "99") (name "unconnected-(PTTIN-Pad1)") (class "Default")
      (node (ref "PTTIN") (pin "1") (pinfunction "1_1") (pintype "unspecified+no_connect"))
    )
    (net (code "100") (name "unconnected-(PTTIN-Pad3)") (class "Default")
      (node (ref "PTTIN") (pin "3") (pinfunction "3_3") (pintype "unspecified+no_connect"))
    )
    (net (code "101") (name "unconnected-(UCLK-C0-Pad7)") (class "Default")
      (node (ref "UCLK") (pin "7") (pinfunction "C0_7") (pintype "unspecified+no_connect"))
    )
    (net (code "102") (name "unconnected-(UCLK-C1-Pad6)") (class "Default")
      (node (ref "UCLK") (pin "6") (pinfunction "C1_6") (pintype "unspecified+no_connect"))
    )
    (net (code "103") (name "unconnected-(UCLK-C2-Pad5)") (class "Default")
      (node (ref "UCLK") (pin "5") (pinfunction "C2_5") (pintype "unspecified+no_connect"))
    )
  )
)
